# Sheet3.net
KiCad netlist of a schematic drawn in Altium Designer
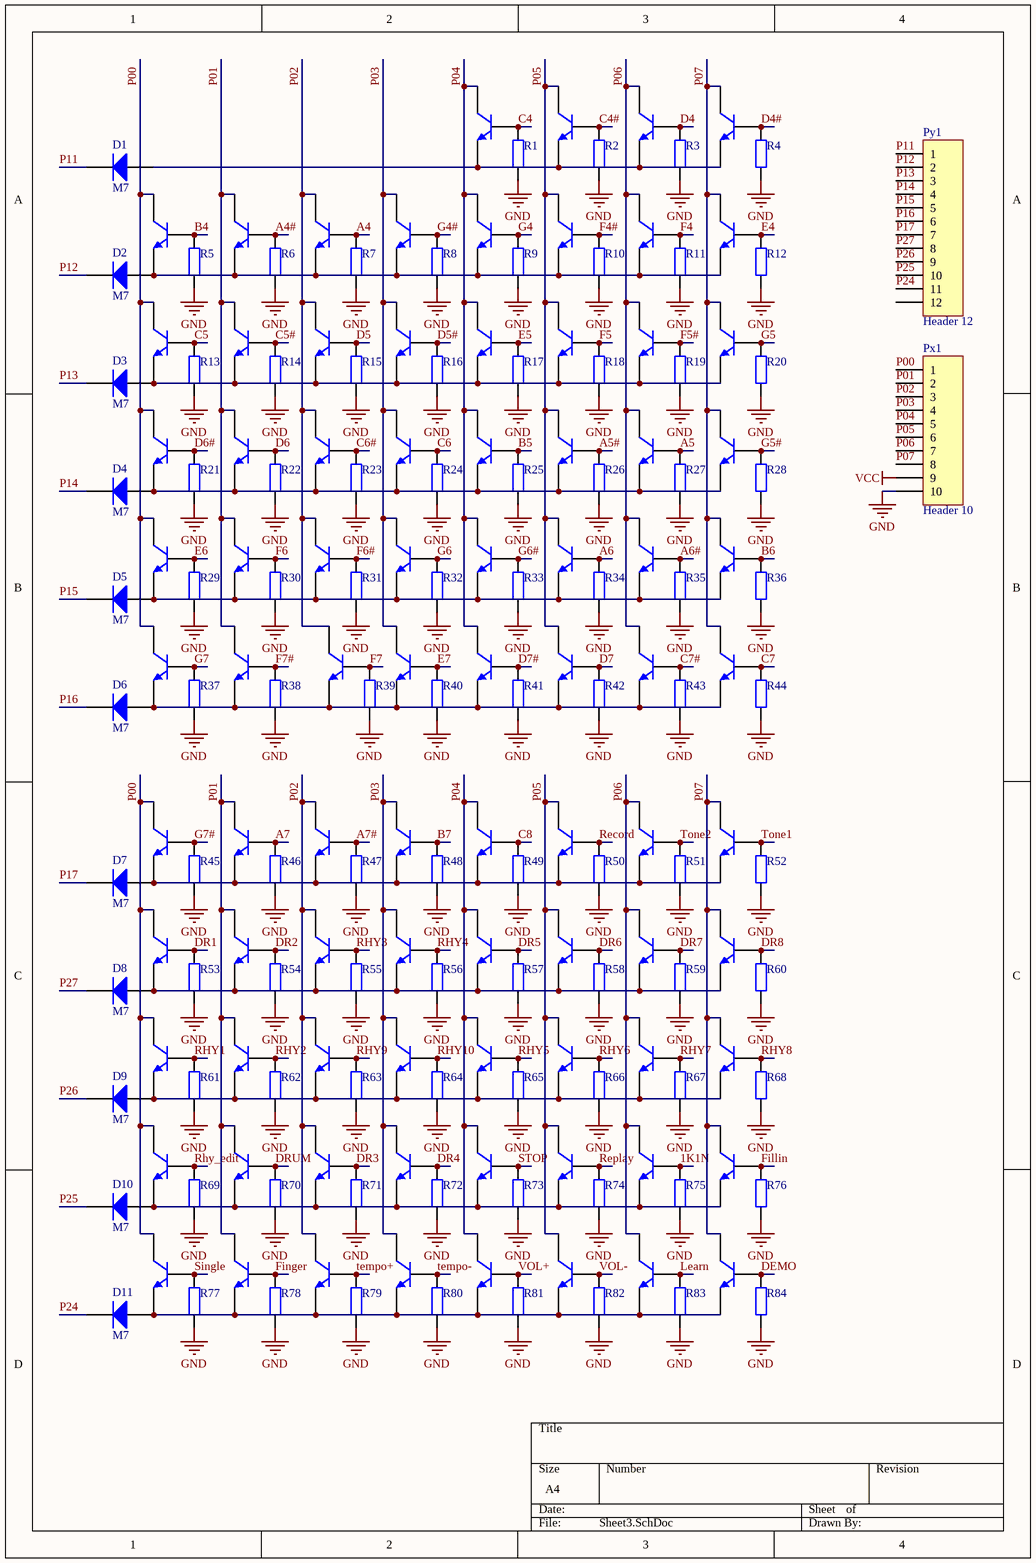
[diagram p0: Sheet3.SchDoc]

(export (version "E")
  (design (tool "Eeschema 10.0.6"))
  (components
    (comp (ref "D1")
      (value "M7")
      (footprint "SMA(DO-214AC)_S1")
      (description "二极管")
      (libsource (lib "Miscellaneous Devices LC") (part "SMA(DO-214AC) M7"))
    )
    (comp (ref "D2")
      (value "M7")
      (footprint "SMA(DO-214AC)_S1")
      (description "二极管")
      (libsource (lib "Miscellaneous Devices LC") (part "SMA(DO-214AC) M7"))
    )
    (comp (ref "D3")
      (value "M7")
      (footprint "SMA(DO-214AC)_S1")
      (description "二极管")
      (libsource (lib "Miscellaneous Devices LC") (part "SMA(DO-214AC) M7"))
    )
    (comp (ref "D4")
      (value "M7")
      (footprint "SMA(DO-214AC)_S1")
      (description "二极管")
      (libsource (lib "Miscellaneous Devices LC") (part "SMA(DO-214AC) M7"))
    )
    (comp (ref "D5")
      (value "M7")
      (footprint "SMA(DO-214AC)_S1")
      (description "二极管")
      (libsource (lib "Miscellaneous Devices LC") (part "SMA(DO-214AC) M7"))
    )
    (comp (ref "D6")
      (value "M7")
      (footprint "SMA(DO-214AC)_S1")
      (description "二极管")
      (libsource (lib "Miscellaneous Devices LC") (part "SMA(DO-214AC) M7"))
    )
    (comp (ref "D7")
      (value "M7")
      (footprint "SMA(DO-214AC)_S1")
      (description "二极管")
      (libsource (lib "Miscellaneous Devices LC") (part "SMA(DO-214AC) M7"))
    )
    (comp (ref "D8")
      (value "M7")
      (footprint "SMA(DO-214AC)_S1")
      (description "二极管")
      (libsource (lib "Miscellaneous Devices LC") (part "SMA(DO-214AC) M7"))
    )
    (comp (ref "D9")
      (value "M7")
      (footprint "SMA(DO-214AC)_S1")
      (description "二极管")
      (libsource (lib "Miscellaneous Devices LC") (part "SMA(DO-214AC) M7"))
    )
    (comp (ref "D10")
      (value "M7")
      (footprint "SMA(DO-214AC)_S1")
      (description "二极管")
      (libsource (lib "Miscellaneous Devices LC") (part "SMA(DO-214AC) M7"))
    )
    (comp (ref "D11")
      (value "M7")
      (footprint "SMA(DO-214AC)_S1")
      (description "二极管")
      (libsource (lib "Miscellaneous Devices LC") (part "SMA(DO-214AC) M7"))
    )
    (comp (ref "Px1")
      (value "Header 10")
      (footprint "FPC1.0-2H-WS-10P")
      (description "Header, 10-Pin")
      (fields (field (name "PUBLISHER") "Altium Limited"))
      (libsource (lib "Miscellaneous Connectors") (part "Header 10"))
    )
    (comp (ref "Py1")
      (value "Header 12")
      (footprint "FPC1.0-2H-WS-12P")
      (description "Header, 12-Pin")
      (fields (field (name "PUBLISHER") "Altium Limited"))
      (libsource (lib "Miscellaneous Connectors") (part "Header 12"))
    )
    (comp (ref "Q1")
      (value "SS8050 Y1")
      (footprint "SOT-23(SOT-23-3)")
      (description "三极管")
      (libsource (lib "Miscellaneous Devices LC") (part "SOT-23 SS8050 Y1"))
    )
    (comp (ref "Q2")
      (value "SS8050 Y1")
      (footprint "SOT-23(SOT-23-3)")
      (description "三极管")
      (libsource (lib "Miscellaneous Devices LC") (part "SOT-23 SS8050 Y1"))
    )
    (comp (ref "Q3")
      (value "SS8050 Y1")
      (footprint "SOT-23(SOT-23-3)")
      (description "三极管")
      (libsource (lib "Miscellaneous Devices LC") (part "SOT-23 SS8050 Y1"))
    )
    (comp (ref "Q4")
      (value "SS8050 Y1")
      (footprint "SOT-23(SOT-23-3)")
      (description "三极管")
      (libsource (lib "Miscellaneous Devices LC") (part "SOT-23 SS8050 Y1"))
    )
    (comp (ref "Q5")
      (value "SS8050 Y1")
      (footprint "SOT-23(SOT-23-3)")
      (description "三极管")
      (libsource (lib "Miscellaneous Devices LC") (part "SOT-23 SS8050 Y1"))
    )
    (comp (ref "Q6")
      (value "SS8050 Y1")
      (footprint "SOT-23(SOT-23-3)")
      (description "三极管")
      (libsource (lib "Miscellaneous Devices LC") (part "SOT-23 SS8050 Y1"))
    )
    (comp (ref "Q7")
      (value "SS8050 Y1")
      (footprint "SOT-23(SOT-23-3)")
      (description "三极管")
      (libsource (lib "Miscellaneous Devices LC") (part "SOT-23 SS8050 Y1"))
    )
    (comp (ref "Q8")
      (value "SS8050 Y1")
      (footprint "SOT-23(SOT-23-3)")
      (description "三极管")
      (libsource (lib "Miscellaneous Devices LC") (part "SOT-23 SS8050 Y1"))
    )
    (comp (ref "Q9")
      (value "SS8050 Y1")
      (footprint "SOT-23(SOT-23-3)")
      (description "三极管")
      (libsource (lib "Miscellaneous Devices LC") (part "SOT-23 SS8050 Y1"))
    )
    (comp (ref "Q10")
      (value "SS8050 Y1")
      (footprint "SOT-23(SOT-23-3)")
      (description "三极管")
      (libsource (lib "Miscellaneous Devices LC") (part "SOT-23 SS8050 Y1"))
    )
    (comp (ref "Q11")
      (value "SS8050 Y1")
      (footprint "SOT-23(SOT-23-3)")
      (description "三极管")
      (libsource (lib "Miscellaneous Devices LC") (part "SOT-23 SS8050 Y1"))
    )
    (comp (ref "Q12")
      (value "SS8050 Y1")
      (footprint "SOT-23(SOT-23-3)")
      (description "三极管")
      (libsource (lib "Miscellaneous Devices LC") (part "SOT-23 SS8050 Y1"))
    )
    (comp (ref "Q13")
      (value "SS8050 Y1")
      (footprint "SOT-23(SOT-23-3)")
      (description "三极管")
      (libsource (lib "Miscellaneous Devices LC") (part "SOT-23 SS8050 Y1"))
    )
    (comp (ref "Q14")
      (value "SS8050 Y1")
      (footprint "SOT-23(SOT-23-3)")
      (description "三极管")
      (libsource (lib "Miscellaneous Devices LC") (part "SOT-23 SS8050 Y1"))
    )
    (comp (ref "Q15")
      (value "SS8050 Y1")
      (footprint "SOT-23(SOT-23-3)")
      (description "三极管")
      (libsource (lib "Miscellaneous Devices LC") (part "SOT-23 SS8050 Y1"))
    )
    (comp (ref "Q16")
      (value "SS8050 Y1")
      (footprint "SOT-23(SOT-23-3)")
      (description "三极管")
      (libsource (lib "Miscellaneous Devices LC") (part "SOT-23 SS8050 Y1"))
    )
    (comp (ref "Q17")
      (value "SS8050 Y1")
      (footprint "SOT-23(SOT-23-3)")
      (description "三极管")
      (libsource (lib "Miscellaneous Devices LC") (part "SOT-23 SS8050 Y1"))
    )
    (comp (ref "Q18")
      (value "SS8050 Y1")
      (footprint "SOT-23(SOT-23-3)")
      (description "三极管")
      (libsource (lib "Miscellaneous Devices LC") (part "SOT-23 SS8050 Y1"))
    )
    (comp (ref "Q19")
      (value "SS8050 Y1")
      (footprint "SOT-23(SOT-23-3)")
      (description "三极管")
      (libsource (lib "Miscellaneous Devices LC") (part "SOT-23 SS8050 Y1"))
    )
    (comp (ref "Q20")
      (value "SS8050 Y1")
      (footprint "SOT-23(SOT-23-3)")
      (description "三极管")
      (libsource (lib "Miscellaneous Devices LC") (part "SOT-23 SS8050 Y1"))
    )
    (comp (ref "Q21")
      (value "SS8050 Y1")
      (footprint "SOT-23(SOT-23-3)")
      (description "三极管")
      (libsource (lib "Miscellaneous Devices LC") (part "SOT-23 SS8050 Y1"))
    )
    (comp (ref "Q22")
      (value "SS8050 Y1")
      (footprint "SOT-23(SOT-23-3)")
      (description "三极管")
      (libsource (lib "Miscellaneous Devices LC") (part "SOT-23 SS8050 Y1"))
    )
    (comp (ref "Q23")
      (value "SS8050 Y1")
      (footprint "SOT-23(SOT-23-3)")
      (description "三极管")
      (libsource (lib "Miscellaneous Devices LC") (part "SOT-23 SS8050 Y1"))
    )
    (comp (ref "Q24")
      (value "SS8050 Y1")
      (footprint "SOT-23(SOT-23-3)")
      (description "三极管")
      (libsource (lib "Miscellaneous Devices LC") (part "SOT-23 SS8050 Y1"))
    )
    (comp (ref "Q25")
      (value "SS8050 Y1")
      (footprint "SOT-23(SOT-23-3)")
      (description "三极管")
      (libsource (lib "Miscellaneous Devices LC") (part "SOT-23 SS8050 Y1"))
    )
    (comp (ref "Q26")
      (value "SS8050 Y1")
      (footprint "SOT-23(SOT-23-3)")
      (description "三极管")
      (libsource (lib "Miscellaneous Devices LC") (part "SOT-23 SS8050 Y1"))
    )
    (comp (ref "Q27")
      (value "SS8050 Y1")
      (footprint "SOT-23(SOT-23-3)")
      (description "三极管")
      (libsource (lib "Miscellaneous Devices LC") (part "SOT-23 SS8050 Y1"))
    )
    (comp (ref "Q28")
      (value "SS8050 Y1")
      (footprint "SOT-23(SOT-23-3)")
      (description "三极管")
      (libsource (lib "Miscellaneous Devices LC") (part "SOT-23 SS8050 Y1"))
    )
    (comp (ref "Q29")
      (value "SS8050 Y1")
      (footprint "SOT-23(SOT-23-3)")
      (description "三极管")
      (libsource (lib "Miscellaneous Devices LC") (part "SOT-23 SS8050 Y1"))
    )
    (comp (ref "Q30")
      (value "SS8050 Y1")
      (footprint "SOT-23(SOT-23-3)")
      (description "三极管")
      (libsource (lib "Miscellaneous Devices LC") (part "SOT-23 SS8050 Y1"))
    )
    (comp (ref "Q31")
      (value "SS8050 Y1")
      (footprint "SOT-23(SOT-23-3)")
      (description "三极管")
      (libsource (lib "Miscellaneous Devices LC") (part "SOT-23 SS8050 Y1"))
    )
    (comp (ref "Q32")
      (value "SS8050 Y1")
      (footprint "SOT-23(SOT-23-3)")
      (description "三极管")
      (libsource (lib "Miscellaneous Devices LC") (part "SOT-23 SS8050 Y1"))
    )
    (comp (ref "Q33")
      (value "SS8050 Y1")
      (footprint "SOT-23(SOT-23-3)")
      (description "三极管")
      (libsource (lib "Miscellaneous Devices LC") (part "SOT-23 SS8050 Y1"))
    )
    (comp (ref "Q34")
      (value "SS8050 Y1")
      (footprint "SOT-23(SOT-23-3)")
      (description "三极管")
      (libsource (lib "Miscellaneous Devices LC") (part "SOT-23 SS8050 Y1"))
    )
    (comp (ref "Q35")
      (value "SS8050 Y1")
      (footprint "SOT-23(SOT-23-3)")
      (description "三极管")
      (libsource (lib "Miscellaneous Devices LC") (part "SOT-23 SS8050 Y1"))
    )
    (comp (ref "Q36")
      (value "SS8050 Y1")
      (footprint "SOT-23(SOT-23-3)")
      (description "三极管")
      (libsource (lib "Miscellaneous Devices LC") (part "SOT-23 SS8050 Y1"))
    )
    (comp (ref "Q37")
      (value "SS8050 Y1")
      (footprint "SOT-23(SOT-23-3)")
      (description "三极管")
      (libsource (lib "Miscellaneous Devices LC") (part "SOT-23 SS8050 Y1"))
    )
    (comp (ref "Q38")
      (value "SS8050 Y1")
      (footprint "SOT-23(SOT-23-3)")
      (description "三极管")
      (libsource (lib "Miscellaneous Devices LC") (part "SOT-23 SS8050 Y1"))
    )
    (comp (ref "Q39")
      (value "SS8050 Y1")
      (footprint "SOT-23(SOT-23-3)")
      (description "三极管")
      (libsource (lib "Miscellaneous Devices LC") (part "SOT-23 SS8050 Y1"))
    )
    (comp (ref "Q40")
      (value "SS8050 Y1")
      (footprint "SOT-23(SOT-23-3)")
      (description "三极管")
      (libsource (lib "Miscellaneous Devices LC") (part "SOT-23 SS8050 Y1"))
    )
    (comp (ref "Q41")
      (value "SS8050 Y1")
      (footprint "SOT-23(SOT-23-3)")
      (description "三极管")
      (libsource (lib "Miscellaneous Devices LC") (part "SOT-23 SS8050 Y1"))
    )
    (comp (ref "Q42")
      (value "SS8050 Y1")
      (footprint "SOT-23(SOT-23-3)")
      (description "三极管")
      (libsource (lib "Miscellaneous Devices LC") (part "SOT-23 SS8050 Y1"))
    )
    (comp (ref "Q43")
      (value "SS8050 Y1")
      (footprint "SOT-23(SOT-23-3)")
      (description "三极管")
      (libsource (lib "Miscellaneous Devices LC") (part "SOT-23 SS8050 Y1"))
    )
    (comp (ref "Q44")
      (value "SS8050 Y1")
      (footprint "SOT-23(SOT-23-3)")
      (description "三极管")
      (libsource (lib "Miscellaneous Devices LC") (part "SOT-23 SS8050 Y1"))
    )
    (comp (ref "Q45")
      (value "SS8050 Y1")
      (footprint "SOT-23(SOT-23-3)")
      (description "三极管")
      (libsource (lib "Miscellaneous Devices LC") (part "SOT-23 SS8050 Y1"))
    )
    (comp (ref "Q46")
      (value "SS8050 Y1")
      (footprint "SOT-23(SOT-23-3)")
      (description "三极管")
      (libsource (lib "Miscellaneous Devices LC") (part "SOT-23 SS8050 Y1"))
    )
    (comp (ref "Q47")
      (value "SS8050 Y1")
      (footprint "SOT-23(SOT-23-3)")
      (description "三极管")
      (libsource (lib "Miscellaneous Devices LC") (part "SOT-23 SS8050 Y1"))
    )
    (comp (ref "Q48")
      (value "SS8050 Y1")
      (footprint "SOT-23(SOT-23-3)")
      (description "三极管")
      (libsource (lib "Miscellaneous Devices LC") (part "SOT-23 SS8050 Y1"))
    )
    (comp (ref "Q49")
      (value "SS8050 Y1")
      (footprint "SOT-23(SOT-23-3)")
      (description "三极管")
      (libsource (lib "Miscellaneous Devices LC") (part "SOT-23 SS8050 Y1"))
    )
    (comp (ref "Q50")
      (value "SS8050 Y1")
      (footprint "SOT-23(SOT-23-3)")
      (description "三极管")
      (libsource (lib "Miscellaneous Devices LC") (part "SOT-23 SS8050 Y1"))
    )
    (comp (ref "Q51")
      (value "SS8050 Y1")
      (footprint "SOT-23(SOT-23-3)")
      (description "三极管")
      (libsource (lib "Miscellaneous Devices LC") (part "SOT-23 SS8050 Y1"))
    )
    (comp (ref "Q52")
      (value "SS8050 Y1")
      (footprint "SOT-23(SOT-23-3)")
      (description "三极管")
      (libsource (lib "Miscellaneous Devices LC") (part "SOT-23 SS8050 Y1"))
    )
    (comp (ref "Q53")
      (value "SS8050 Y1")
      (footprint "SOT-23(SOT-23-3)")
      (description "三极管")
      (libsource (lib "Miscellaneous Devices LC") (part "SOT-23 SS8050 Y1"))
    )
    (comp (ref "Q54")
      (value "SS8050 Y1")
      (footprint "SOT-23(SOT-23-3)")
      (description "三极管")
      (libsource (lib "Miscellaneous Devices LC") (part "SOT-23 SS8050 Y1"))
    )
    (comp (ref "Q55")
      (value "SS8050 Y1")
      (footprint "SOT-23(SOT-23-3)")
      (description "三极管")
      (libsource (lib "Miscellaneous Devices LC") (part "SOT-23 SS8050 Y1"))
    )
    (comp (ref "Q56")
      (value "SS8050 Y1")
      (footprint "SOT-23(SOT-23-3)")
      (description "三极管")
      (libsource (lib "Miscellaneous Devices LC") (part "SOT-23 SS8050 Y1"))
    )
    (comp (ref "Q57")
      (value "SS8050 Y1")
      (footprint "SOT-23(SOT-23-3)")
      (description "三极管")
      (libsource (lib "Miscellaneous Devices LC") (part "SOT-23 SS8050 Y1"))
    )
    (comp (ref "Q58")
      (value "SS8050 Y1")
      (footprint "SOT-23(SOT-23-3)")
      (description "三极管")
      (libsource (lib "Miscellaneous Devices LC") (part "SOT-23 SS8050 Y1"))
    )
    (comp (ref "Q59")
      (value "SS8050 Y1")
      (footprint "SOT-23(SOT-23-3)")
      (description "三极管")
      (libsource (lib "Miscellaneous Devices LC") (part "SOT-23 SS8050 Y1"))
    )
    (comp (ref "Q60")
      (value "SS8050 Y1")
      (footprint "SOT-23(SOT-23-3)")
      (description "三极管")
      (libsource (lib "Miscellaneous Devices LC") (part "SOT-23 SS8050 Y1"))
    )
    (comp (ref "Q61")
      (value "SS8050 Y1")
      (footprint "SOT-23(SOT-23-3)")
      (description "三极管")
      (libsource (lib "Miscellaneous Devices LC") (part "SOT-23 SS8050 Y1"))
    )
    (comp (ref "Q62")
      (value "SS8050 Y1")
      (footprint "SOT-23(SOT-23-3)")
      (description "三极管")
      (libsource (lib "Miscellaneous Devices LC") (part "SOT-23 SS8050 Y1"))
    )
    (comp (ref "Q63")
      (value "SS8050 Y1")
      (footprint "SOT-23(SOT-23-3)")
      (description "三极管")
      (libsource (lib "Miscellaneous Devices LC") (part "SOT-23 SS8050 Y1"))
    )
    (comp (ref "Q64")
      (value "SS8050 Y1")
      (footprint "SOT-23(SOT-23-3)")
      (description "三极管")
      (libsource (lib "Miscellaneous Devices LC") (part "SOT-23 SS8050 Y1"))
    )
    (comp (ref "Q65")
      (value "SS8050 Y1")
      (footprint "SOT-23(SOT-23-3)")
      (description "三极管")
      (libsource (lib "Miscellaneous Devices LC") (part "SOT-23 SS8050 Y1"))
    )
    (comp (ref "Q66")
      (value "SS8050 Y1")
      (footprint "SOT-23(SOT-23-3)")
      (description "三极管")
      (libsource (lib "Miscellaneous Devices LC") (part "SOT-23 SS8050 Y1"))
    )
    (comp (ref "Q67")
      (value "SS8050 Y1")
      (footprint "SOT-23(SOT-23-3)")
      (description "三极管")
      (libsource (lib "Miscellaneous Devices LC") (part "SOT-23 SS8050 Y1"))
    )
    (comp (ref "Q68")
      (value "SS8050 Y1")
      (footprint "SOT-23(SOT-23-3)")
      (description "三极管")
      (libsource (lib "Miscellaneous Devices LC") (part "SOT-23 SS8050 Y1"))
    )
    (comp (ref "Q69")
      (value "SS8050 Y1")
      (footprint "SOT-23(SOT-23-3)")
      (description "三极管")
      (libsource (lib "Miscellaneous Devices LC") (part "SOT-23 SS8050 Y1"))
    )
    (comp (ref "Q70")
      (value "SS8050 Y1")
      (footprint "SOT-23(SOT-23-3)")
      (description "三极管")
      (libsource (lib "Miscellaneous Devices LC") (part "SOT-23 SS8050 Y1"))
    )
    (comp (ref "Q71")
      (value "SS8050 Y1")
      (footprint "SOT-23(SOT-23-3)")
      (description "三极管")
      (libsource (lib "Miscellaneous Devices LC") (part "SOT-23 SS8050 Y1"))
    )
    (comp (ref "Q72")
      (value "SS8050 Y1")
      (footprint "SOT-23(SOT-23-3)")
      (description "三极管")
      (libsource (lib "Miscellaneous Devices LC") (part "SOT-23 SS8050 Y1"))
    )
    (comp (ref "Q73")
      (value "SS8050 Y1")
      (footprint "SOT-23(SOT-23-3)")
      (description "三极管")
      (libsource (lib "Miscellaneous Devices LC") (part "SOT-23 SS8050 Y1"))
    )
    (comp (ref "Q74")
      (value "SS8050 Y1")
      (footprint "SOT-23(SOT-23-3)")
      (description "三极管")
      (libsource (lib "Miscellaneous Devices LC") (part "SOT-23 SS8050 Y1"))
    )
    (comp (ref "Q75")
      (value "SS8050 Y1")
      (footprint "SOT-23(SOT-23-3)")
      (description "三极管")
      (libsource (lib "Miscellaneous Devices LC") (part "SOT-23 SS8050 Y1"))
    )
    (comp (ref "Q76")
      (value "SS8050 Y1")
      (footprint "SOT-23(SOT-23-3)")
      (description "三极管")
      (libsource (lib "Miscellaneous Devices LC") (part "SOT-23 SS8050 Y1"))
    )
    (comp (ref "Q77")
      (value "SS8050 Y1")
      (footprint "SOT-23(SOT-23-3)")
      (description "三极管")
      (libsource (lib "Miscellaneous Devices LC") (part "SOT-23 SS8050 Y1"))
    )
    (comp (ref "Q78")
      (value "SS8050 Y1")
      (footprint "SOT-23(SOT-23-3)")
      (description "三极管")
      (libsource (lib "Miscellaneous Devices LC") (part "SOT-23 SS8050 Y1"))
    )
    (comp (ref "Q79")
      (value "SS8050 Y1")
      (footprint "SOT-23(SOT-23-3)")
      (description "三极管")
      (libsource (lib "Miscellaneous Devices LC") (part "SOT-23 SS8050 Y1"))
    )
    (comp (ref "Q80")
      (value "SS8050 Y1")
      (footprint "SOT-23(SOT-23-3)")
      (description "三极管")
      (libsource (lib "Miscellaneous Devices LC") (part "SOT-23 SS8050 Y1"))
    )
    (comp (ref "Q81")
      (value "SS8050 Y1")
      (footprint "SOT-23(SOT-23-3)")
      (description "三极管")
      (libsource (lib "Miscellaneous Devices LC") (part "SOT-23 SS8050 Y1"))
    )
    (comp (ref "Q82")
      (value "SS8050 Y1")
      (footprint "SOT-23(SOT-23-3)")
      (description "三极管")
      (libsource (lib "Miscellaneous Devices LC") (part "SOT-23 SS8050 Y1"))
    )
    (comp (ref "Q83")
      (value "SS8050 Y1")
      (footprint "SOT-23(SOT-23-3)")
      (description "三极管")
      (libsource (lib "Miscellaneous Devices LC") (part "SOT-23 SS8050 Y1"))
    )
    (comp (ref "Q84")
      (value "SS8050 Y1")
      (footprint "SOT-23(SOT-23-3)")
      (description "三极管")
      (libsource (lib "Miscellaneous Devices LC") (part "SOT-23 SS8050 Y1"))
    )
    (comp (ref "R1")
      (value "10KΩ (1002) ±1%")
      (footprint "0603_R")
      (description "贴片电阻")
      (libsource (lib "Miscellaneous Devices LC") (part "0603 10KΩ (1002) 1%"))
    )
    (comp (ref "R2")
      (value "10KΩ (1002) ±1%")
      (footprint "0603_R")
      (description "贴片电阻")
      (libsource (lib "Miscellaneous Devices LC") (part "0603 10KΩ (1002) 1%"))
    )
    (comp (ref "R3")
      (value "10KΩ (1002) ±1%")
      (footprint "0603_R")
      (description "贴片电阻")
      (libsource (lib "Miscellaneous Devices LC") (part "0603 10KΩ (1002) 1%"))
    )
    (comp (ref "R4")
      (value "10KΩ (1002) ±1%")
      (footprint "0603_R")
      (description "贴片电阻")
      (libsource (lib "Miscellaneous Devices LC") (part "0603 10KΩ (1002) 1%"))
    )
    (comp (ref "R5")
      (value "10KΩ (1002) ±1%")
      (footprint "0603_R")
      (description "贴片电阻")
      (libsource (lib "Miscellaneous Devices LC") (part "0603 10KΩ (1002) 1%"))
    )
    (comp (ref "R6")
      (value "10KΩ (1002) ±1%")
      (footprint "0603_R")
      (description "贴片电阻")
      (libsource (lib "Miscellaneous Devices LC") (part "0603 10KΩ (1002) 1%"))
    )
    (comp (ref "R7")
      (value "10KΩ (1002) ±1%")
      (footprint "0603_R")
      (description "贴片电阻")
      (libsource (lib "Miscellaneous Devices LC") (part "0603 10KΩ (1002) 1%"))
    )
    (comp (ref "R8")
      (value "10KΩ (1002) ±1%")
      (footprint "0603_R")
      (description "贴片电阻")
      (libsource (lib "Miscellaneous Devices LC") (part "0603 10KΩ (1002) 1%"))
    )
    (comp (ref "R9")
      (value "10KΩ (1002) ±1%")
      (footprint "0603_R")
      (description "贴片电阻")
      (libsource (lib "Miscellaneous Devices LC") (part "0603 10KΩ (1002) 1%"))
    )
    (comp (ref "R10")
      (value "10KΩ (1002) ±1%")
      (footprint "0603_R")
      (description "贴片电阻")
      (libsource (lib "Miscellaneous Devices LC") (part "0603 10KΩ (1002) 1%"))
    )
    (comp (ref "R11")
      (value "10KΩ (1002) ±1%")
      (footprint "0603_R")
      (description "贴片电阻")
      (libsource (lib "Miscellaneous Devices LC") (part "0603 10KΩ (1002) 1%"))
    )
    (comp (ref "R12")
      (value "10KΩ (1002) ±1%")
      (footprint "0603_R")
      (description "贴片电阻")
      (libsource (lib "Miscellaneous Devices LC") (part "0603 10KΩ (1002) 1%"))
    )
    (comp (ref "R13")
      (value "10KΩ (1002) ±1%")
      (footprint "0603_R")
      (description "贴片电阻")
      (libsource (lib "Miscellaneous Devices LC") (part "0603 10KΩ (1002) 1%"))
    )
    (comp (ref "R14")
      (value "10KΩ (1002) ±1%")
      (footprint "0603_R")
      (description "贴片电阻")
      (libsource (lib "Miscellaneous Devices LC") (part "0603 10KΩ (1002) 1%"))
    )
    (comp (ref "R15")
      (value "10KΩ (1002) ±1%")
      (footprint "0603_R")
      (description "贴片电阻")
      (libsource (lib "Miscellaneous Devices LC") (part "0603 10KΩ (1002) 1%"))
    )
    (comp (ref "R16")
      (value "10KΩ (1002) ±1%")
      (footprint "0603_R")
      (description "贴片电阻")
      (libsource (lib "Miscellaneous Devices LC") (part "0603 10KΩ (1002) 1%"))
    )
    (comp (ref "R17")
      (value "10KΩ (1002) ±1%")
      (footprint "0603_R")
      (description "贴片电阻")
      (libsource (lib "Miscellaneous Devices LC") (part "0603 10KΩ (1002) 1%"))
    )
    (comp (ref "R18")
      (value "10KΩ (1002) ±1%")
      (footprint "0603_R")
      (description "贴片电阻")
      (libsource (lib "Miscellaneous Devices LC") (part "0603 10KΩ (1002) 1%"))
    )
    (comp (ref "R19")
      (value "10KΩ (1002) ±1%")
      (footprint "0603_R")
      (description "贴片电阻")
      (libsource (lib "Miscellaneous Devices LC") (part "0603 10KΩ (1002) 1%"))
    )
    (comp (ref "R20")
      (value "10KΩ (1002) ±1%")
      (footprint "0603_R")
      (description "贴片电阻")
      (libsource (lib "Miscellaneous Devices LC") (part "0603 10KΩ (1002) 1%"))
    )
    (comp (ref "R21")
      (value "10KΩ (1002) ±1%")
      (footprint "0603_R")
      (description "贴片电阻")
      (libsource (lib "Miscellaneous Devices LC") (part "0603 10KΩ (1002) 1%"))
    )
    (comp (ref "R22")
      (value "10KΩ (1002) ±1%")
      (footprint "0603_R")
      (description "贴片电阻")
      (libsource (lib "Miscellaneous Devices LC") (part "0603 10KΩ (1002) 1%"))
    )
    (comp (ref "R23")
      (value "10KΩ (1002) ±1%")
      (footprint "0603_R")
      (description "贴片电阻")
      (libsource (lib "Miscellaneous Devices LC") (part "0603 10KΩ (1002) 1%"))
    )
    (comp (ref "R24")
      (value "10KΩ (1002) ±1%")
      (footprint "0603_R")
      (description "贴片电阻")
      (libsource (lib "Miscellaneous Devices LC") (part "0603 10KΩ (1002) 1%"))
    )
    (comp (ref "R25")
      (value "10KΩ (1002) ±1%")
      (footprint "0603_R")
      (description "贴片电阻")
      (libsource (lib "Miscellaneous Devices LC") (part "0603 10KΩ (1002) 1%"))
    )
    (comp (ref "R26")
      (value "10KΩ (1002) ±1%")
      (footprint "0603_R")
      (description "贴片电阻")
      (libsource (lib "Miscellaneous Devices LC") (part "0603 10KΩ (1002) 1%"))
    )
    (comp (ref "R27")
      (value "10KΩ (1002) ±1%")
      (footprint "0603_R")
      (description "贴片电阻")
      (libsource (lib "Miscellaneous Devices LC") (part "0603 10KΩ (1002) 1%"))
    )
    (comp (ref "R28")
      (value "10KΩ (1002) ±1%")
      (footprint "0603_R")
      (description "贴片电阻")
      (libsource (lib "Miscellaneous Devices LC") (part "0603 10KΩ (1002) 1%"))
    )
    (comp (ref "R29")
      (value "10KΩ (1002) ±1%")
      (footprint "0603_R")
      (description "贴片电阻")
      (libsource (lib "Miscellaneous Devices LC") (part "0603 10KΩ (1002) 1%"))
    )
    (comp (ref "R30")
      (value "10KΩ (1002) ±1%")
      (footprint "0603_R")
      (description "贴片电阻")
      (libsource (lib "Miscellaneous Devices LC") (part "0603 10KΩ (1002) 1%"))
    )
    (comp (ref "R31")
      (value "10KΩ (1002) ±1%")
      (footprint "0603_R")
      (description "贴片电阻")
      (libsource (lib "Miscellaneous Devices LC") (part "0603 10KΩ (1002) 1%"))
    )
    (comp (ref "R32")
      (value "10KΩ (1002) ±1%")
      (footprint "0603_R")
      (description "贴片电阻")
      (libsource (lib "Miscellaneous Devices LC") (part "0603 10KΩ (1002) 1%"))
    )
    (comp (ref "R33")
      (value "10KΩ (1002) ±1%")
      (footprint "0603_R")
      (description "贴片电阻")
      (libsource (lib "Miscellaneous Devices LC") (part "0603 10KΩ (1002) 1%"))
    )
    (comp (ref "R34")
      (value "10KΩ (1002) ±1%")
      (footprint "0603_R")
      (description "贴片电阻")
      (libsource (lib "Miscellaneous Devices LC") (part "0603 10KΩ (1002) 1%"))
    )
    (comp (ref "R35")
      (value "10KΩ (1002) ±1%")
      (footprint "0603_R")
      (description "贴片电阻")
      (libsource (lib "Miscellaneous Devices LC") (part "0603 10KΩ (1002) 1%"))
    )
    (comp (ref "R36")
      (value "10KΩ (1002) ±1%")
      (footprint "0603_R")
      (description "贴片电阻")
      (libsource (lib "Miscellaneous Devices LC") (part "0603 10KΩ (1002) 1%"))
    )
    (comp (ref "R37")
      (value "10KΩ (1002) ±1%")
      (footprint "0603_R")
      (description "贴片电阻")
      (libsource (lib "Miscellaneous Devices LC") (part "0603 10KΩ (1002) 1%"))
    )
    (comp (ref "R38")
      (value "10KΩ (1002) ±1%")
      (footprint "0603_R")
      (description "贴片电阻")
      (libsource (lib "Miscellaneous Devices LC") (part "0603 10KΩ (1002) 1%"))
    )
    (comp (ref "R39")
      (value "10KΩ (1002) ±1%")
      (footprint "0603_R")
      (description "贴片电阻")
      (libsource (lib "Miscellaneous Devices LC") (part "0603 10KΩ (1002) 1%"))
    )
    (comp (ref "R40")
      (value "10KΩ (1002) ±1%")
      (footprint "0603_R")
      (description "贴片电阻")
      (libsource (lib "Miscellaneous Devices LC") (part "0603 10KΩ (1002) 1%"))
    )
    (comp (ref "R41")
      (value "10KΩ (1002) ±1%")
      (footprint "0603_R")
      (description "贴片电阻")
      (libsource (lib "Miscellaneous Devices LC") (part "0603 10KΩ (1002) 1%"))
    )
    (comp (ref "R42")
      (value "10KΩ (1002) ±1%")
      (footprint "0603_R")
      (description "贴片电阻")
      (libsource (lib "Miscellaneous Devices LC") (part "0603 10KΩ (1002) 1%"))
    )
    (comp (ref "R43")
      (value "10KΩ (1002) ±1%")
      (footprint "0603_R")
      (description "贴片电阻")
      (libsource (lib "Miscellaneous Devices LC") (part "0603 10KΩ (1002) 1%"))
    )
    (comp (ref "R44")
      (value "10KΩ (1002) ±1%")
      (footprint "0603_R")
      (description "贴片电阻")
      (libsource (lib "Miscellaneous Devices LC") (part "0603 10KΩ (1002) 1%"))
    )
    (comp (ref "R45")
      (value "10KΩ (1002) ±1%")
      (footprint "0603_R")
      (description "贴片电阻")
      (libsource (lib "Miscellaneous Devices LC") (part "0603 10KΩ (1002) 1%"))
    )
    (comp (ref "R46")
      (value "10KΩ (1002) ±1%")
      (footprint "0603_R")
      (description "贴片电阻")
      (libsource (lib "Miscellaneous Devices LC") (part "0603 10KΩ (1002) 1%"))
    )
    (comp (ref "R47")
      (value "10KΩ (1002) ±1%")
      (footprint "0603_R")
      (description "贴片电阻")
      (libsource (lib "Miscellaneous Devices LC") (part "0603 10KΩ (1002) 1%"))
    )
    (comp (ref "R48")
      (value "10KΩ (1002) ±1%")
      (footprint "0603_R")
      (description "贴片电阻")
      (libsource (lib "Miscellaneous Devices LC") (part "0603 10KΩ (1002) 1%"))
    )
    (comp (ref "R49")
      (value "10KΩ (1002) ±1%")
      (footprint "0603_R")
      (description "贴片电阻")
      (libsource (lib "Miscellaneous Devices LC") (part "0603 10KΩ (1002) 1%"))
    )
    (comp (ref "R50")
      (value "10KΩ (1002) ±1%")
      (footprint "0603_R")
      (description "贴片电阻")
      (libsource (lib "Miscellaneous Devices LC") (part "0603 10KΩ (1002) 1%"))
    )
    (comp (ref "R51")
      (value "10KΩ (1002) ±1%")
      (footprint "0603_R")
      (description "贴片电阻")
      (libsource (lib "Miscellaneous Devices LC") (part "0603 10KΩ (1002) 1%"))
    )
    (comp (ref "R52")
      (value "10KΩ (1002) ±1%")
      (footprint "0603_R")
      (description "贴片电阻")
      (libsource (lib "Miscellaneous Devices LC") (part "0603 10KΩ (1002) 1%"))
    )
    (comp (ref "R53")
      (value "10KΩ (1002) ±1%")
      (footprint "0603_R")
      (description "贴片电阻")
      (libsource (lib "Miscellaneous Devices LC") (part "0603 10KΩ (1002) 1%"))
    )
    (comp (ref "R54")
      (value "10KΩ (1002) ±1%")
      (footprint "0603_R")
      (description "贴片电阻")
      (libsource (lib "Miscellaneous Devices LC") (part "0603 10KΩ (1002) 1%"))
    )
    (comp (ref "R55")
      (value "10KΩ (1002) ±1%")
      (footprint "0603_R")
      (description "贴片电阻")
      (libsource (lib "Miscellaneous Devices LC") (part "0603 10KΩ (1002) 1%"))
    )
    (comp (ref "R56")
      (value "10KΩ (1002) ±1%")
      (footprint "0603_R")
      (description "贴片电阻")
      (libsource (lib "Miscellaneous Devices LC") (part "0603 10KΩ (1002) 1%"))
    )
    (comp (ref "R57")
      (value "10KΩ (1002) ±1%")
      (footprint "0603_R")
      (description "贴片电阻")
      (libsource (lib "Miscellaneous Devices LC") (part "0603 10KΩ (1002) 1%"))
    )
    (comp (ref "R58")
      (value "10KΩ (1002) ±1%")
      (footprint "0603_R")
      (description "贴片电阻")
      (libsource (lib "Miscellaneous Devices LC") (part "0603 10KΩ (1002) 1%"))
    )
    (comp (ref "R59")
      (value "10KΩ (1002) ±1%")
      (footprint "0603_R")
      (description "贴片电阻")
      (libsource (lib "Miscellaneous Devices LC") (part "0603 10KΩ (1002) 1%"))
    )
    (comp (ref "R60")
      (value "10KΩ (1002) ±1%")
      (footprint "0603_R")
      (description "贴片电阻")
      (libsource (lib "Miscellaneous Devices LC") (part "0603 10KΩ (1002) 1%"))
    )
    (comp (ref "R61")
      (value "10KΩ (1002) ±1%")
      (footprint "0603_R")
      (description "贴片电阻")
      (libsource (lib "Miscellaneous Devices LC") (part "0603 10KΩ (1002) 1%"))
    )
    (comp (ref "R62")
      (value "10KΩ (1002) ±1%")
      (footprint "0603_R")
      (description "贴片电阻")
      (libsource (lib "Miscellaneous Devices LC") (part "0603 10KΩ (1002) 1%"))
    )
    (comp (ref "R63")
      (value "10KΩ (1002) ±1%")
      (footprint "0603_R")
      (description "贴片电阻")
      (libsource (lib "Miscellaneous Devices LC") (part "0603 10KΩ (1002) 1%"))
    )
    (comp (ref "R64")
      (value "10KΩ (1002) ±1%")
      (footprint "0603_R")
      (description "贴片电阻")
      (libsource (lib "Miscellaneous Devices LC") (part "0603 10KΩ (1002) 1%"))
    )
    (comp (ref "R65")
      (value "10KΩ (1002) ±1%")
      (footprint "0603_R")
      (description "贴片电阻")
      (libsource (lib "Miscellaneous Devices LC") (part "0603 10KΩ (1002) 1%"))
    )
    (comp (ref "R66")
      (value "10KΩ (1002) ±1%")
      (footprint "0603_R")
      (description "贴片电阻")
      (libsource (lib "Miscellaneous Devices LC") (part "0603 10KΩ (1002) 1%"))
    )
    (comp (ref "R67")
      (value "10KΩ (1002) ±1%")
      (footprint "0603_R")
      (description "贴片电阻")
      (libsource (lib "Miscellaneous Devices LC") (part "0603 10KΩ (1002) 1%"))
    )
    (comp (ref "R68")
      (value "10KΩ (1002) ±1%")
      (footprint "0603_R")
      (description "贴片电阻")
      (libsource (lib "Miscellaneous Devices LC") (part "0603 10KΩ (1002) 1%"))
    )
    (comp (ref "R69")
      (value "10KΩ (1002) ±1%")
      (footprint "0603_R")
      (description "贴片电阻")
      (libsource (lib "Miscellaneous Devices LC") (part "0603 10KΩ (1002) 1%"))
    )
    (comp (ref "R70")
      (value "10KΩ (1002) ±1%")
      (footprint "0603_R")
      (description "贴片电阻")
      (libsource (lib "Miscellaneous Devices LC") (part "0603 10KΩ (1002) 1%"))
    )
    (comp (ref "R71")
      (value "10KΩ (1002) ±1%")
      (footprint "0603_R")
      (description "贴片电阻")
      (libsource (lib "Miscellaneous Devices LC") (part "0603 10KΩ (1002) 1%"))
    )
    (comp (ref "R72")
      (value "10KΩ (1002) ±1%")
      (footprint "0603_R")
      (description "贴片电阻")
      (libsource (lib "Miscellaneous Devices LC") (part "0603 10KΩ (1002) 1%"))
    )
    (comp (ref "R73")
      (value "10KΩ (1002) ±1%")
      (footprint "0603_R")
      (description "贴片电阻")
      (libsource (lib "Miscellaneous Devices LC") (part "0603 10KΩ (1002) 1%"))
    )
    (comp (ref "R74")
      (value "10KΩ (1002) ±1%")
      (footprint "0603_R")
      (description "贴片电阻")
      (libsource (lib "Miscellaneous Devices LC") (part "0603 10KΩ (1002) 1%"))
    )
    (comp (ref "R75")
      (value "10KΩ (1002) ±1%")
      (footprint "0603_R")
      (description "贴片电阻")
      (libsource (lib "Miscellaneous Devices LC") (part "0603 10KΩ (1002) 1%"))
    )
    (comp (ref "R76")
      (value "10KΩ (1002) ±1%")
      (footprint "0603_R")
      (description "贴片电阻")
      (libsource (lib "Miscellaneous Devices LC") (part "0603 10KΩ (1002) 1%"))
    )
    (comp (ref "R77")
      (value "10KΩ (1002) ±1%")
      (footprint "0603_R")
      (description "贴片电阻")
      (libsource (lib "Miscellaneous Devices LC") (part "0603 10KΩ (1002) 1%"))
    )
    (comp (ref "R78")
      (value "10KΩ (1002) ±1%")
      (footprint "0603_R")
      (description "贴片电阻")
      (libsource (lib "Miscellaneous Devices LC") (part "0603 10KΩ (1002) 1%"))
    )
    (comp (ref "R79")
      (value "10KΩ (1002) ±1%")
      (footprint "0603_R")
      (description "贴片电阻")
      (libsource (lib "Miscellaneous Devices LC") (part "0603 10KΩ (1002) 1%"))
    )
    (comp (ref "R80")
      (value "10KΩ (1002) ±1%")
      (footprint "0603_R")
      (description "贴片电阻")
      (libsource (lib "Miscellaneous Devices LC") (part "0603 10KΩ (1002) 1%"))
    )
    (comp (ref "R81")
      (value "10KΩ (1002) ±1%")
      (footprint "0603_R")
      (description "贴片电阻")
      (libsource (lib "Miscellaneous Devices LC") (part "0603 10KΩ (1002) 1%"))
    )
    (comp (ref "R82")
      (value "10KΩ (1002) ±1%")
      (footprint "0603_R")
      (description "贴片电阻")
      (libsource (lib "Miscellaneous Devices LC") (part "0603 10KΩ (1002) 1%"))
    )
    (comp (ref "R83")
      (value "10KΩ (1002) ±1%")
      (footprint "0603_R")
      (description "贴片电阻")
      (libsource (lib "Miscellaneous Devices LC") (part "0603 10KΩ (1002) 1%"))
    )
    (comp (ref "R84")
      (value "10KΩ (1002) ±1%")
      (footprint "0603_R")
      (description "贴片电阻")
      (libsource (lib "Miscellaneous Devices LC") (part "0603 10KΩ (1002) 1%"))
    )
  )
  (nets
    (net (code "1") (name "/1K1N") (class "Default")
      (node (ref "Q75") (pin "1") (pinfunction "B_1") (pintype "passive"))
      (node (ref "R75") (pin "2") (pinfunction "2_2") (pintype "passive"))
    )
    (net (code "2") (name "/A4") (class "Default")
      (node (ref "Q7") (pin "1") (pinfunction "B_1") (pintype "passive"))
      (node (ref "R7") (pin "2") (pinfunction "2_2") (pintype "passive"))
    )
    (net (code "3") (name "/A4#") (class "Default")
      (node (ref "Q6") (pin "1") (pinfunction "B_1") (pintype "passive"))
      (node (ref "R6") (pin "2") (pinfunction "2_2") (pintype "passive"))
    )
    (net (code "4") (name "/A5") (class "Default")
      (node (ref "Q27") (pin "1") (pinfunction "B_1") (pintype "passive"))
      (node (ref "R27") (pin "2") (pinfunction "2_2") (pintype "passive"))
    )
    (net (code "5") (name "/A5#") (class "Default")
      (node (ref "Q26") (pin "1") (pinfunction "B_1") (pintype "passive"))
      (node (ref "R26") (pin "2") (pinfunction "2_2") (pintype "passive"))
    )
    (net (code "6") (name "/A6") (class "Default")
      (node (ref "Q34") (pin "1") (pinfunction "B_1") (pintype "passive"))
      (node (ref "R34") (pin "2") (pinfunction "2_2") (pintype "passive"))
    )
    (net (code "7") (name "/A6#") (class "Default")
      (node (ref "Q35") (pin "1") (pinfunction "B_1") (pintype "passive"))
      (node (ref "R35") (pin "2") (pinfunction "2_2") (pintype "passive"))
    )
    (net (code "8") (name "/A7") (class "Default")
      (node (ref "Q46") (pin "1") (pinfunction "B_1") (pintype "passive"))
      (node (ref "R46") (pin "2") (pinfunction "2_2") (pintype "passive"))
    )
    (net (code "9") (name "/A7#") (class "Default")
      (node (ref "Q47") (pin "1") (pinfunction "B_1") (pintype "passive"))
      (node (ref "R47") (pin "2") (pinfunction "2_2") (pintype "passive"))
    )
    (net (code "10") (name "/B4") (class "Default")
      (node (ref "Q5") (pin "1") (pinfunction "B_1") (pintype "passive"))
      (node (ref "R5") (pin "2") (pinfunction "2_2") (pintype "passive"))
    )
    (net (code "11") (name "/B5") (class "Default")
      (node (ref "Q25") (pin "1") (pinfunction "B_1") (pintype "passive"))
      (node (ref "R25") (pin "2") (pinfunction "2_2") (pintype "passive"))
    )
    (net (code "12") (name "/B6") (class "Default")
      (node (ref "Q36") (pin "1") (pinfunction "B_1") (pintype "passive"))
      (node (ref "R36") (pin "2") (pinfunction "2_2") (pintype "passive"))
    )
    (net (code "13") (name "/B7") (class "Default")
      (node (ref "Q48") (pin "1") (pinfunction "B_1") (pintype "passive"))
      (node (ref "R48") (pin "2") (pinfunction "2_2") (pintype "passive"))
    )
    (net (code "14") (name "/C4") (class "Default")
      (node (ref "Q1") (pin "1") (pinfunction "B_1") (pintype "passive"))
      (node (ref "R1") (pin "2") (pinfunction "2_2") (pintype "passive"))
    )
    (net (code "15") (name "/C4#") (class "Default")
      (node (ref "Q2") (pin "1") (pinfunction "B_1") (pintype "passive"))
      (node (ref "R2") (pin "2") (pinfunction "2_2") (pintype "passive"))
    )
    (net (code "16") (name "/C5") (class "Default")
      (node (ref "Q13") (pin "1") (pinfunction "B_1") (pintype "passive"))
      (node (ref "R13") (pin "2") (pinfunction "2_2") (pintype "passive"))
    )
    (net (code "17") (name "/C5#") (class "Default")
      (node (ref "Q14") (pin "1") (pinfunction "B_1") (pintype "passive"))
      (node (ref "R14") (pin "2") (pinfunction "2_2") (pintype "passive"))
    )
    (net (code "18") (name "/C6") (class "Default")
      (node (ref "Q24") (pin "1") (pinfunction "B_1") (pintype "passive"))
      (node (ref "R24") (pin "2") (pinfunction "2_2") (pintype "passive"))
    )
    (net (code "19") (name "/C6#") (class "Default")
      (node (ref "Q23") (pin "1") (pinfunction "B_1") (pintype "passive"))
      (node (ref "R23") (pin "2") (pinfunction "2_2") (pintype "passive"))
    )
    (net (code "20") (name "/C7") (class "Default")
      (node (ref "Q44") (pin "1") (pinfunction "B_1") (pintype "passive"))
      (node (ref "R44") (pin "2") (pinfunction "2_2") (pintype "passive"))
    )
    (net (code "21") (name "/C7#") (class "Default")
      (node (ref "Q43") (pin "1") (pinfunction "B_1") (pintype "passive"))
      (node (ref "R43") (pin "2") (pinfunction "2_2") (pintype "passive"))
    )
    (net (code "22") (name "/C8") (class "Default")
      (node (ref "Q49") (pin "1") (pinfunction "B_1") (pintype "passive"))
      (node (ref "R49") (pin "2") (pinfunction "2_2") (pintype "passive"))
    )
    (net (code "23") (name "/D4") (class "Default")
      (node (ref "Q3") (pin "1") (pinfunction "B_1") (pintype "passive"))
      (node (ref "R3") (pin "2") (pinfunction "2_2") (pintype "passive"))
    )
    (net (code "24") (name "/D4#") (class "Default")
      (node (ref "Q4") (pin "1") (pinfunction "B_1") (pintype "passive"))
      (node (ref "R4") (pin "2") (pinfunction "2_2") (pintype "passive"))
    )
    (net (code "25") (name "/D5") (class "Default")
      (node (ref "Q15") (pin "1") (pinfunction "B_1") (pintype "passive"))
      (node (ref "R15") (pin "2") (pinfunction "2_2") (pintype "passive"))
    )
    (net (code "26") (name "/D5#") (class "Default")
      (node (ref "Q16") (pin "1") (pinfunction "B_1") (pintype "passive"))
      (node (ref "R16") (pin "2") (pinfunction "2_2") (pintype "passive"))
    )
    (net (code "27") (name "/D6") (class "Default")
      (node (ref "Q22") (pin "1") (pinfunction "B_1") (pintype "passive"))
      (node (ref "R22") (pin "2") (pinfunction "2_2") (pintype "passive"))
    )
    (net (code "28") (name "/D6#") (class "Default")
      (node (ref "Q21") (pin "1") (pinfunction "B_1") (pintype "passive"))
      (node (ref "R21") (pin "2") (pinfunction "2_2") (pintype "passive"))
    )
    (net (code "29") (name "/D7") (class "Default")
      (node (ref "Q42") (pin "1") (pinfunction "B_1") (pintype "passive"))
      (node (ref "R42") (pin "2") (pinfunction "2_2") (pintype "passive"))
    )
    (net (code "30") (name "/D7#") (class "Default")
      (node (ref "Q41") (pin "1") (pinfunction "B_1") (pintype "passive"))
      (node (ref "R41") (pin "2") (pinfunction "2_2") (pintype "passive"))
    )
    (net (code "31") (name "/DEMO") (class "Default")
      (node (ref "Q84") (pin "1") (pinfunction "B_1") (pintype "passive"))
      (node (ref "R84") (pin "2") (pinfunction "2_2") (pintype "passive"))
    )
    (net (code "32") (name "/DR1") (class "Default")
      (node (ref "Q53") (pin "1") (pinfunction "B_1") (pintype "passive"))
      (node (ref "R53") (pin "2") (pinfunction "2_2") (pintype "passive"))
    )
    (net (code "33") (name "/DR2") (class "Default")
      (node (ref "Q54") (pin "1") (pinfunction "B_1") (pintype "passive"))
      (node (ref "R54") (pin "2") (pinfunction "2_2") (pintype "passive"))
    )
    (net (code "34") (name "/DR3") (class "Default")
      (node (ref "Q71") (pin "1") (pinfunction "B_1") (pintype "passive"))
      (node (ref "R71") (pin "2") (pinfunction "2_2") (pintype "passive"))
    )
    (net (code "35") (name "/DR4") (class "Default")
      (node (ref "Q72") (pin "1") (pinfunction "B_1") (pintype "passive"))
      (node (ref "R72") (pin "2") (pinfunction "2_2") (pintype "passive"))
    )
    (net (code "36") (name "/DR5") (class "Default")
      (node (ref "Q57") (pin "1") (pinfunction "B_1") (pintype "passive"))
      (node (ref "R57") (pin "2") (pinfunction "2_2") (pintype "passive"))
    )
    (net (code "37") (name "/DR6") (class "Default")
      (node (ref "Q58") (pin "1") (pinfunction "B_1") (pintype "passive"))
      (node (ref "R58") (pin "2") (pinfunction "2_2") (pintype "passive"))
    )
    (net (code "38") (name "/DR7") (class "Default")
      (node (ref "Q59") (pin "1") (pinfunction "B_1") (pintype "passive"))
      (node (ref "R59") (pin "2") (pinfunction "2_2") (pintype "passive"))
    )
    (net (code "39") (name "/DR8") (class "Default")
      (node (ref "Q60") (pin "1") (pinfunction "B_1") (pintype "passive"))
      (node (ref "R60") (pin "2") (pinfunction "2_2") (pintype "passive"))
    )
    (net (code "40") (name "/DRUM") (class "Default")
      (node (ref "Q70") (pin "1") (pinfunction "B_1") (pintype "passive"))
      (node (ref "R70") (pin "2") (pinfunction "2_2") (pintype "passive"))
    )
    (net (code "41") (name "/E4") (class "Default")
      (node (ref "Q12") (pin "1") (pinfunction "B_1") (pintype "passive"))
      (node (ref "R12") (pin "2") (pinfunction "2_2") (pintype "passive"))
    )
    (net (code "42") (name "/E5") (class "Default")
      (node (ref "Q17") (pin "1") (pinfunction "B_1") (pintype "passive"))
      (node (ref "R17") (pin "2") (pinfunction "2_2") (pintype "passive"))
    )
    (net (code "43") (name "/E6") (class "Default")
      (node (ref "Q29") (pin "1") (pinfunction "B_1") (pintype "passive"))
      (node (ref "R29") (pin "2") (pinfunction "2_2") (pintype "passive"))
    )
    (net (code "44") (name "/E7") (class "Default")
      (node (ref "Q40") (pin "1") (pinfunction "B_1") (pintype "passive"))
      (node (ref "R40") (pin "2") (pinfunction "2_2") (pintype "passive"))
    )
    (net (code "45") (name "/F4") (class "Default")
      (node (ref "Q11") (pin "1") (pinfunction "B_1") (pintype "passive"))
      (node (ref "R11") (pin "2") (pinfunction "2_2") (pintype "passive"))
    )
    (net (code "46") (name "/F4#") (class "Default")
      (node (ref "Q10") (pin "1") (pinfunction "B_1") (pintype "passive"))
      (node (ref "R10") (pin "2") (pinfunction "2_2") (pintype "passive"))
    )
    (net (code "47") (name "/F5") (class "Default")
      (node (ref "Q18") (pin "1") (pinfunction "B_1") (pintype "passive"))
      (node (ref "R18") (pin "2") (pinfunction "2_2") (pintype "passive"))
    )
    (net (code "48") (name "/F5#") (class "Default")
      (node (ref "Q19") (pin "1") (pinfunction "B_1") (pintype "passive"))
      (node (ref "R19") (pin "2") (pinfunction "2_2") (pintype "passive"))
    )
    (net (code "49") (name "/F6") (class "Default")
      (node (ref "Q30") (pin "1") (pinfunction "B_1") (pintype "passive"))
      (node (ref "R30") (pin "2") (pinfunction "2_2") (pintype "passive"))
    )
    (net (code "50") (name "/F6#") (class "Default")
      (node (ref "Q31") (pin "1") (pinfunction "B_1") (pintype "passive"))
      (node (ref "R31") (pin "2") (pinfunction "2_2") (pintype "passive"))
    )
    (net (code "51") (name "/F7") (class "Default")
      (node (ref "Q39") (pin "1") (pinfunction "B_1") (pintype "passive"))
      (node (ref "R39") (pin "2") (pinfunction "2_2") (pintype "passive"))
    )
    (net (code "52") (name "/F7#") (class "Default")
      (node (ref "Q38") (pin "1") (pinfunction "B_1") (pintype "passive"))
      (node (ref "R38") (pin "2") (pinfunction "2_2") (pintype "passive"))
    )
    (net (code "53") (name "/Fillin") (class "Default")
      (node (ref "Q76") (pin "1") (pinfunction "B_1") (pintype "passive"))
      (node (ref "R76") (pin "2") (pinfunction "2_2") (pintype "passive"))
    )
    (net (code "54") (name "/Finger") (class "Default")
      (node (ref "Q78") (pin "1") (pinfunction "B_1") (pintype "passive"))
      (node (ref "R78") (pin "2") (pinfunction "2_2") (pintype "passive"))
    )
    (net (code "55") (name "/G4") (class "Default")
      (node (ref "Q9") (pin "1") (pinfunction "B_1") (pintype "passive"))
      (node (ref "R9") (pin "2") (pinfunction "2_2") (pintype "passive"))
    )
    (net (code "56") (name "/G4#") (class "Default")
      (node (ref "Q8") (pin "1") (pinfunction "B_1") (pintype "passive"))
      (node (ref "R8") (pin "2") (pinfunction "2_2") (pintype "passive"))
    )
    (net (code "57") (name "/G5") (class "Default")
      (node (ref "Q20") (pin "1") (pinfunction "B_1") (pintype "passive"))
      (node (ref "R20") (pin "2") (pinfunction "2_2") (pintype "passive"))
    )
    (net (code "58") (name "/G5#") (class "Default")
      (node (ref "Q28") (pin "1") (pinfunction "B_1") (pintype "passive"))
      (node (ref "R28") (pin "2") (pinfunction "2_2") (pintype "passive"))
    )
    (net (code "59") (name "/G6") (class "Default")
      (node (ref "Q32") (pin "1") (pinfunction "B_1") (pintype "passive"))
      (node (ref "R32") (pin "2") (pinfunction "2_2") (pintype "passive"))
    )
    (net (code "60") (name "/G6#") (class "Default")
      (node (ref "Q33") (pin "1") (pinfunction "B_1") (pintype "passive"))
      (node (ref "R33") (pin "2") (pinfunction "2_2") (pintype "passive"))
    )
    (net (code "61") (name "/G7") (class "Default")
      (node (ref "Q37") (pin "1") (pinfunction "B_1") (pintype "passive"))
      (node (ref "R37") (pin "2") (pinfunction "2_2") (pintype "passive"))
    )
    (net (code "62") (name "/G7#") (class "Default")
      (node (ref "Q45") (pin "1") (pinfunction "B_1") (pintype "passive"))
      (node (ref "R45") (pin "2") (pinfunction "2_2") (pintype "passive"))
    )
    (net (code "63") (name "/Learn") (class "Default")
      (node (ref "Q83") (pin "1") (pinfunction "B_1") (pintype "passive"))
      (node (ref "R83") (pin "2") (pinfunction "2_2") (pintype "passive"))
    )
    (net (code "64") (name "/P00") (class "Default")
      (node (ref "Px1") (pin "1") (pinfunction "1_1") (pintype "passive"))
      (node (ref "Q13") (pin "3") (pinfunction "C_3") (pintype "passive"))
      (node (ref "Q21") (pin "3") (pinfunction "C_3") (pintype "passive"))
      (node (ref "Q29") (pin "3") (pinfunction "C_3") (pintype "passive"))
      (node (ref "Q37") (pin "3") (pinfunction "C_3") (pintype "passive"))
      (node (ref "Q45") (pin "3") (pinfunction "C_3") (pintype "passive"))
      (node (ref "Q5") (pin "3") (pinfunction "C_3") (pintype "passive"))
      (node (ref "Q53") (pin "3") (pinfunction "C_3") (pintype "passive"))
      (node (ref "Q61") (pin "3") (pinfunction "C_3") (pintype "passive"))
      (node (ref "Q69") (pin "3") (pinfunction "C_3") (pintype "passive"))
      (node (ref "Q77") (pin "3") (pinfunction "C_3") (pintype "passive"))
    )
    (net (code "65") (name "/P01") (class "Default")
      (node (ref "Px1") (pin "2") (pinfunction "2_2") (pintype "passive"))
      (node (ref "Q14") (pin "3") (pinfunction "C_3") (pintype "passive"))
      (node (ref "Q22") (pin "3") (pinfunction "C_3") (pintype "passive"))
      (node (ref "Q30") (pin "3") (pinfunction "C_3") (pintype "passive"))
      (node (ref "Q38") (pin "3") (pinfunction "C_3") (pintype "passive"))
      (node (ref "Q46") (pin "3") (pinfunction "C_3") (pintype "passive"))
      (node (ref "Q54") (pin "3") (pinfunction "C_3") (pintype "passive"))
      (node (ref "Q6") (pin "3") (pinfunction "C_3") (pintype "passive"))
      (node (ref "Q62") (pin "3") (pinfunction "C_3") (pintype "passive"))
      (node (ref "Q70") (pin "3") (pinfunction "C_3") (pintype "passive"))
      (node (ref "Q78") (pin "3") (pinfunction "C_3") (pintype "passive"))
    )
    (net (code "66") (name "/P02") (class "Default")
      (node (ref "Px1") (pin "3") (pinfunction "3_3") (pintype "passive"))
      (node (ref "Q15") (pin "3") (pinfunction "C_3") (pintype "passive"))
      (node (ref "Q23") (pin "3") (pinfunction "C_3") (pintype "passive"))
      (node (ref "Q31") (pin "3") (pinfunction "C_3") (pintype "passive"))
      (node (ref "Q39") (pin "3") (pinfunction "C_3") (pintype "passive"))
      (node (ref "Q47") (pin "3") (pinfunction "C_3") (pintype "passive"))
      (node (ref "Q55") (pin "3") (pinfunction "C_3") (pintype "passive"))
      (node (ref "Q63") (pin "3") (pinfunction "C_3") (pintype "passive"))
      (node (ref "Q7") (pin "3") (pinfunction "C_3") (pintype "passive"))
      (node (ref "Q71") (pin "3") (pinfunction "C_3") (pintype "passive"))
      (node (ref "Q79") (pin "3") (pinfunction "C_3") (pintype "passive"))
    )
    (net (code "67") (name "/P03") (class "Default")
      (node (ref "Px1") (pin "4") (pinfunction "4_4") (pintype "passive"))
      (node (ref "Q16") (pin "3") (pinfunction "C_3") (pintype "passive"))
      (node (ref "Q24") (pin "3") (pinfunction "C_3") (pintype "passive"))
      (node (ref "Q32") (pin "3") (pinfunction "C_3") (pintype "passive"))
      (node (ref "Q40") (pin "3") (pinfunction "C_3") (pintype "passive"))
      (node (ref "Q48") (pin "3") (pinfunction "C_3") (pintype "passive"))
      (node (ref "Q56") (pin "3") (pinfunction "C_3") (pintype "passive"))
      (node (ref "Q64") (pin "3") (pinfunction "C_3") (pintype "passive"))
      (node (ref "Q72") (pin "3") (pinfunction "C_3") (pintype "passive"))
      (node (ref "Q8") (pin "3") (pinfunction "C_3") (pintype "passive"))
      (node (ref "Q80") (pin "3") (pinfunction "C_3") (pintype "passive"))
    )
    (net (code "68") (name "/P04") (class "Default")
      (node (ref "Px1") (pin "5") (pinfunction "5_5") (pintype "passive"))
      (node (ref "Q1") (pin "3") (pinfunction "C_3") (pintype "passive"))
      (node (ref "Q17") (pin "3") (pinfunction "C_3") (pintype "passive"))
      (node (ref "Q25") (pin "3") (pinfunction "C_3") (pintype "passive"))
      (node (ref "Q33") (pin "3") (pinfunction "C_3") (pintype "passive"))
      (node (ref "Q41") (pin "3") (pinfunction "C_3") (pintype "passive"))
      (node (ref "Q49") (pin "3") (pinfunction "C_3") (pintype "passive"))
      (node (ref "Q57") (pin "3") (pinfunction "C_3") (pintype "passive"))
      (node (ref "Q65") (pin "3") (pinfunction "C_3") (pintype "passive"))
      (node (ref "Q73") (pin "3") (pinfunction "C_3") (pintype "passive"))
      (node (ref "Q81") (pin "3") (pinfunction "C_3") (pintype "passive"))
      (node (ref "Q9") (pin "3") (pinfunction "C_3") (pintype "passive"))
    )
    (net (code "69") (name "/P05") (class "Default")
      (node (ref "Px1") (pin "6") (pinfunction "6_6") (pintype "passive"))
      (node (ref "Q10") (pin "3") (pinfunction "C_3") (pintype "passive"))
      (node (ref "Q18") (pin "3") (pinfunction "C_3") (pintype "passive"))
      (node (ref "Q2") (pin "3") (pinfunction "C_3") (pintype "passive"))
      (node (ref "Q26") (pin "3") (pinfunction "C_3") (pintype "passive"))
      (node (ref "Q34") (pin "3") (pinfunction "C_3") (pintype "passive"))
      (node (ref "Q42") (pin "3") (pinfunction "C_3") (pintype "passive"))
      (node (ref "Q50") (pin "3") (pinfunction "C_3") (pintype "passive"))
      (node (ref "Q58") (pin "3") (pinfunction "C_3") (pintype "passive"))
      (node (ref "Q66") (pin "3") (pinfunction "C_3") (pintype "passive"))
      (node (ref "Q74") (pin "3") (pinfunction "C_3") (pintype "passive"))
      (node (ref "Q82") (pin "3") (pinfunction "C_3") (pintype "passive"))
    )
    (net (code "70") (name "/P06") (class "Default")
      (node (ref "Px1") (pin "7") (pinfunction "7_7") (pintype "passive"))
      (node (ref "Q11") (pin "3") (pinfunction "C_3") (pintype "passive"))
      (node (ref "Q19") (pin "3") (pinfunction "C_3") (pintype "passive"))
      (node (ref "Q27") (pin "3") (pinfunction "C_3") (pintype "passive"))
      (node (ref "Q3") (pin "3") (pinfunction "C_3") (pintype "passive"))
      (node (ref "Q35") (pin "3") (pinfunction "C_3") (pintype "passive"))
      (node (ref "Q43") (pin "3") (pinfunction "C_3") (pintype "passive"))
      (node (ref "Q51") (pin "3") (pinfunction "C_3") (pintype "passive"))
      (node (ref "Q59") (pin "3") (pinfunction "C_3") (pintype "passive"))
      (node (ref "Q67") (pin "3") (pinfunction "C_3") (pintype "passive"))
      (node (ref "Q75") (pin "3") (pinfunction "C_3") (pintype "passive"))
      (node (ref "Q83") (pin "3") (pinfunction "C_3") (pintype "passive"))
    )
    (net (code "71") (name "/P07") (class "Default")
      (node (ref "Px1") (pin "8") (pinfunction "8_8") (pintype "passive"))
      (node (ref "Q12") (pin "3") (pinfunction "C_3") (pintype "passive"))
      (node (ref "Q20") (pin "3") (pinfunction "C_3") (pintype "passive"))
      (node (ref "Q28") (pin "3") (pinfunction "C_3") (pintype "passive"))
      (node (ref "Q36") (pin "3") (pinfunction "C_3") (pintype "passive"))
      (node (ref "Q4") (pin "3") (pinfunction "C_3") (pintype "passive"))
      (node (ref "Q44") (pin "3") (pinfunction "C_3") (pintype "passive"))
      (node (ref "Q52") (pin "3") (pinfunction "C_3") (pintype "passive"))
      (node (ref "Q60") (pin "3") (pinfunction "C_3") (pintype "passive"))
      (node (ref "Q68") (pin "3") (pinfunction "C_3") (pintype "passive"))
      (node (ref "Q76") (pin "3") (pinfunction "C_3") (pintype "passive"))
      (node (ref "Q84") (pin "3") (pinfunction "C_3") (pintype "passive"))
    )
    (net (code "72") (name "/P11") (class "Default")
      (node (ref "D1") (pin "2") (pinfunction "K_2") (pintype "passive"))
      (node (ref "Py1") (pin "1") (pinfunction "1_1") (pintype "passive"))
    )
    (net (code "73") (name "/P12") (class "Default")
      (node (ref "D2") (pin "2") (pinfunction "K_2") (pintype "passive"))
      (node (ref "Py1") (pin "2") (pinfunction "2_2") (pintype "passive"))
    )
    (net (code "74") (name "/P13") (class "Default")
      (node (ref "D3") (pin "2") (pinfunction "K_2") (pintype "passive"))
      (node (ref "Py1") (pin "3") (pinfunction "3_3") (pintype "passive"))
    )
    (net (code "75") (name "/P14") (class "Default")
      (node (ref "D4") (pin "2") (pinfunction "K_2") (pintype "passive"))
      (node (ref "Py1") (pin "4") (pinfunction "4_4") (pintype "passive"))
    )
    (net (code "76") (name "/P15") (class "Default")
      (node (ref "D5") (pin "2") (pinfunction "K_2") (pintype "passive"))
      (node (ref "Py1") (pin "5") (pinfunction "5_5") (pintype "passive"))
    )
    (net (code "77") (name "/P16") (class "Default")
      (node (ref "D6") (pin "2") (pinfunction "K_2") (pintype "passive"))
      (node (ref "Py1") (pin "6") (pinfunction "6_6") (pintype "passive"))
    )
    (net (code "78") (name "/P17") (class "Default")
      (node (ref "D7") (pin "2") (pinfunction "K_2") (pintype "passive"))
      (node (ref "Py1") (pin "7") (pinfunction "7_7") (pintype "passive"))
    )
    (net (code "79") (name "/P24") (class "Default")
      (node (ref "D11") (pin "2") (pinfunction "K_2") (pintype "passive"))
      (node (ref "Py1") (pin "11") (pinfunction "11_11") (pintype "passive"))
    )
    (net (code "80") (name "/P25") (class "Default")
      (node (ref "D10") (pin "2") (pinfunction "K_2") (pintype "passive"))
      (node (ref "Py1") (pin "10") (pinfunction "10_10") (pintype "passive"))
    )
    (net (code "81") (name "/P26") (class "Default")
      (node (ref "D9") (pin "2") (pinfunction "K_2") (pintype "passive"))
      (node (ref "Py1") (pin "9") (pinfunction "9_9") (pintype "passive"))
    )
    (net (code "82") (name "/P27") (class "Default")
      (node (ref "D8") (pin "2") (pinfunction "K_2") (pintype "passive"))
      (node (ref "Py1") (pin "8") (pinfunction "8_8") (pintype "passive"))
    )
    (net (code "83") (name "/RHY1") (class "Default")
      (node (ref "Q61") (pin "1") (pinfunction "B_1") (pintype "passive"))
      (node (ref "R61") (pin "2") (pinfunction "2_2") (pintype "passive"))
    )
    (net (code "84") (name "/RHY2") (class "Default")
      (node (ref "Q62") (pin "1") (pinfunction "B_1") (pintype "passive"))
      (node (ref "R62") (pin "2") (pinfunction "2_2") (pintype "passive"))
    )
    (net (code "85") (name "/RHY3") (class "Default")
      (node (ref "Q55") (pin "1") (pinfunction "B_1") (pintype "passive"))
      (node (ref "R55") (pin "2") (pinfunction "2_2") (pintype "passive"))
    )
    (net (code "86") (name "/RHY4") (class "Default")
      (node (ref "Q56") (pin "1") (pinfunction "B_1") (pintype "passive"))
      (node (ref "R56") (pin "2") (pinfunction "2_2") (pintype "passive"))
    )
    (net (code "87") (name "/RHY5") (class "Default")
      (node (ref "Q65") (pin "1") (pinfunction "B_1") (pintype "passive"))
      (node (ref "R65") (pin "2") (pinfunction "2_2") (pintype "passive"))
    )
    (net (code "88") (name "/RHY6") (class "Default")
      (node (ref "Q66") (pin "1") (pinfunction "B_1") (pintype "passive"))
      (node (ref "R66") (pin "2") (pinfunction "2_2") (pintype "passive"))
    )
    (net (code "89") (name "/RHY7") (class "Default")
      (node (ref "Q67") (pin "1") (pinfunction "B_1") (pintype "passive"))
      (node (ref "R67") (pin "2") (pinfunction "2_2") (pintype "passive"))
    )
    (net (code "90") (name "/RHY8") (class "Default")
      (node (ref "Q68") (pin "1") (pinfunction "B_1") (pintype "passive"))
      (node (ref "R68") (pin "2") (pinfunction "2_2") (pintype "passive"))
    )
    (net (code "91") (name "/RHY9") (class "Default")
      (node (ref "Q63") (pin "1") (pinfunction "B_1") (pintype "passive"))
      (node (ref "R63") (pin "2") (pinfunction "2_2") (pintype "passive"))
    )
    (net (code "92") (name "/RHY10") (class "Default")
      (node (ref "Q64") (pin "1") (pinfunction "B_1") (pintype "passive"))
      (node (ref "R64") (pin "2") (pinfunction "2_2") (pintype "passive"))
    )
    (net (code "93") (name "/Record") (class "Default")
      (node (ref "Q50") (pin "1") (pinfunction "B_1") (pintype "passive"))
      (node (ref "R50") (pin "2") (pinfunction "2_2") (pintype "passive"))
    )
    (net (code "94") (name "/Replay") (class "Default")
      (node (ref "Q74") (pin "1") (pinfunction "B_1") (pintype "passive"))
      (node (ref "R74") (pin "2") (pinfunction "2_2") (pintype "passive"))
    )
    (net (code "95") (name "/Rhy_edit") (class "Default")
      (node (ref "Q69") (pin "1") (pinfunction "B_1") (pintype "passive"))
      (node (ref "R69") (pin "2") (pinfunction "2_2") (pintype "passive"))
    )
    (net (code "96") (name "/STOP") (class "Default")
      (node (ref "Q73") (pin "1") (pinfunction "B_1") (pintype "passive"))
      (node (ref "R73") (pin "2") (pinfunction "2_2") (pintype "passive"))
    )
    (net (code "97") (name "/Single") (class "Default")
      (node (ref "Q77") (pin "1") (pinfunction "B_1") (pintype "passive"))
      (node (ref "R77") (pin "2") (pinfunction "2_2") (pintype "passive"))
    )
    (net (code "98") (name "/Tone1") (class "Default")
      (node (ref "Q52") (pin "1") (pinfunction "B_1") (pintype "passive"))
      (node (ref "R52") (pin "2") (pinfunction "2_2") (pintype "passive"))
    )
    (net (code "99") (name "/Tone2") (class "Default")
      (node (ref "Q51") (pin "1") (pinfunction "B_1") (pintype "passive"))
      (node (ref "R51") (pin "2") (pinfunction "2_2") (pintype "passive"))
    )
    (net (code "100") (name "/VOL+") (class "Default")
      (node (ref "Q81") (pin "1") (pinfunction "B_1") (pintype "passive"))
      (node (ref "R81") (pin "2") (pinfunction "2_2") (pintype "passive"))
    )
    (net (code "101") (name "/VOL-") (class "Default")
      (node (ref "Q82") (pin "1") (pinfunction "B_1") (pintype "passive"))
      (node (ref "R82") (pin "2") (pinfunction "2_2") (pintype "passive"))
    )
    (net (code "102") (name "/tempo+") (class "Default")
      (node (ref "Q79") (pin "1") (pinfunction "B_1") (pintype "passive"))
      (node (ref "R79") (pin "2") (pinfunction "2_2") (pintype "passive"))
    )
    (net (code "103") (name "/tempo-") (class "Default")
      (node (ref "Q80") (pin "1") (pinfunction "B_1") (pintype "passive"))
      (node (ref "R80") (pin "2") (pinfunction "2_2") (pintype "passive"))
    )
    (net (code "104") (name "GND") (class "Default")
      (node (ref "Px1") (pin "10") (pinfunction "10_10") (pintype "passive"))
      (node (ref "R1") (pin "1") (pinfunction "1_1") (pintype "passive"))
      (node (ref "R10") (pin "1") (pinfunction "1_1") (pintype "passive"))
      (node (ref "R11") (pin "1") (pinfunction "1_1") (pintype "passive"))
      (node (ref "R12") (pin "1") (pinfunction "1_1") (pintype "passive"))
      (node (ref "R13") (pin "1") (pinfunction "1_1") (pintype "passive"))
      (node (ref "R14") (pin "1") (pinfunction "1_1") (pintype "passive"))
      (node (ref "R15") (pin "1") (pinfunction "1_1") (pintype "passive"))
      (node (ref "R16") (pin "1") (pinfunction "1_1") (pintype "passive"))
      (node (ref "R17") (pin "1") (pinfunction "1_1") (pintype "passive"))
      (node (ref "R18") (pin "1") (pinfunction "1_1") (pintype "passive"))
      (node (ref "R19") (pin "1") (pinfunction "1_1") (pintype "passive"))
      (node (ref "R2") (pin "1") (pinfunction "1_1") (pintype "passive"))
      (node (ref "R20") (pin "1") (pinfunction "1_1") (pintype "passive"))
      (node (ref "R21") (pin "1") (pinfunction "1_1") (pintype "passive"))
      (node (ref "R22") (pin "1") (pinfunction "1_1") (pintype "passive"))
      (node (ref "R23") (pin "1") (pinfunction "1_1") (pintype "passive"))
      (node (ref "R24") (pin "1") (pinfunction "1_1") (pintype "passive"))
      (node (ref "R25") (pin "1") (pinfunction "1_1") (pintype "passive"))
      (node (ref "R26") (pin "1") (pinfunction "1_1") (pintype "passive"))
      (node (ref "R27") (pin "1") (pinfunction "1_1") (pintype "passive"))
      (node (ref "R28") (pin "1") (pinfunction "1_1") (pintype "passive"))
      (node (ref "R29") (pin "1") (pinfunction "1_1") (pintype "passive"))
      (node (ref "R3") (pin "1") (pinfunction "1_1") (pintype "passive"))
      (node (ref "R30") (pin "1") (pinfunction "1_1") (pintype "passive"))
      (node (ref "R31") (pin "1") (pinfunction "1_1") (pintype "passive"))
      (node (ref "R32") (pin "1") (pinfunction "1_1") (pintype "passive"))
      (node (ref "R33") (pin "1") (pinfunction "1_1") (pintype "passive"))
      (node (ref "R34") (pin "1") (pinfunction "1_1") (pintype "passive"))
      (node (ref "R35") (pin "1") (pinfunction "1_1") (pintype "passive"))
      (node (ref "R36") (pin "1") (pinfunction "1_1") (pintype "passive"))
      (node (ref "R37") (pin "1") (pinfunction "1_1") (pintype "passive"))
      (node (ref "R38") (pin "1") (pinfunction "1_1") (pintype "passive"))
      (node (ref "R39") (pin "1") (pinfunction "1_1") (pintype "passive"))
      (node (ref "R4") (pin "1") (pinfunction "1_1") (pintype "passive"))
      (node (ref "R40") (pin "1") (pinfunction "1_1") (pintype "passive"))
      (node (ref "R41") (pin "1") (pinfunction "1_1") (pintype "passive"))
      (node (ref "R42") (pin "1") (pinfunction "1_1") (pintype "passive"))
      (node (ref "R43") (pin "1") (pinfunction "1_1") (pintype "passive"))
      (node (ref "R44") (pin "1") (pinfunction "1_1") (pintype "passive"))
      (node (ref "R45") (pin "1") (pinfunction "1_1") (pintype "passive"))
      (node (ref "R46") (pin "1") (pinfunction "1_1") (pintype "passive"))
      (node (ref "R47") (pin "1") (pinfunction "1_1") (pintype "passive"))
      (node (ref "R48") (pin "1") (pinfunction "1_1") (pintype "passive"))
      (node (ref "R49") (pin "1") (pinfunction "1_1") (pintype "passive"))
      (node (ref "R5") (pin "1") (pinfunction "1_1") (pintype "passive"))
      (node (ref "R50") (pin "1") (pinfunction "1_1") (pintype "passive"))
      (node (ref "R51") (pin "1") (pinfunction "1_1") (pintype "passive"))
      (node (ref "R52") (pin "1") (pinfunction "1_1") (pintype "passive"))
      (node (ref "R53") (pin "1") (pinfunction "1_1") (pintype "passive"))
      (node (ref "R54") (pin "1") (pinfunction "1_1") (pintype "passive"))
      (node (ref "R55") (pin "1") (pinfunction "1_1") (pintype "passive"))
      (node (ref "R56") (pin "1") (pinfunction "1_1") (pintype "passive"))
      (node (ref "R57") (pin "1") (pinfunction "1_1") (pintype "passive"))
      (node (ref "R58") (pin "1") (pinfunction "1_1") (pintype "passive"))
      (node (ref "R59") (pin "1") (pinfunction "1_1") (pintype "passive"))
      (node (ref "R6") (pin "1") (pinfunction "1_1") (pintype "passive"))
      (node (ref "R60") (pin "1") (pinfunction "1_1") (pintype "passive"))
      (node (ref "R61") (pin "1") (pinfunction "1_1") (pintype "passive"))
      (node (ref "R62") (pin "1") (pinfunction "1_1") (pintype "passive"))
      (node (ref "R63") (pin "1") (pinfunction "1_1") (pintype "passive"))
      (node (ref "R64") (pin "1") (pinfunction "1_1") (pintype "passive"))
      (node (ref "R65") (pin "1") (pinfunction "1_1") (pintype "passive"))
      (node (ref "R66") (pin "1") (pinfunction "1_1") (pintype "passive"))
      (node (ref "R67") (pin "1") (pinfunction "1_1") (pintype "passive"))
      (node (ref "R68") (pin "1") (pinfunction "1_1") (pintype "passive"))
      (node (ref "R69") (pin "1") (pinfunction "1_1") (pintype "passive"))
      (node (ref "R7") (pin "1") (pinfunction "1_1") (pintype "passive"))
      (node (ref "R70") (pin "1") (pinfunction "1_1") (pintype "passive"))
      (node (ref "R71") (pin "1") (pinfunction "1_1") (pintype "passive"))
      (node (ref "R72") (pin "1") (pinfunction "1_1") (pintype "passive"))
      (node (ref "R73") (pin "1") (pinfunction "1_1") (pintype "passive"))
      (node (ref "R74") (pin "1") (pinfunction "1_1") (pintype "passive"))
      (node (ref "R75") (pin "1") (pinfunction "1_1") (pintype "passive"))
      (node (ref "R76") (pin "1") (pinfunction "1_1") (pintype "passive"))
      (node (ref "R77") (pin "1") (pinfunction "1_1") (pintype "passive"))
      (node (ref "R78") (pin "1") (pinfunction "1_1") (pintype "passive"))
      (node (ref "R79") (pin "1") (pinfunction "1_1") (pintype "passive"))
      (node (ref "R8") (pin "1") (pinfunction "1_1") (pintype "passive"))
      (node (ref "R80") (pin "1") (pinfunction "1_1") (pintype "passive"))
      (node (ref "R81") (pin "1") (pinfunction "1_1") (pintype "passive"))
      (node (ref "R82") (pin "1") (pinfunction "1_1") (pintype "passive"))
      (node (ref "R83") (pin "1") (pinfunction "1_1") (pintype "passive"))
      (node (ref "R84") (pin "1") (pinfunction "1_1") (pintype "passive"))
      (node (ref "R9") (pin "1") (pinfunction "1_1") (pintype "passive"))
    )
    (net (code "105") (name "Net-(D1-A)") (class "Default")
      (node (ref "D1") (pin "1") (pinfunction "A_1") (pintype "passive"))
      (node (ref "Q1") (pin "2") (pinfunction "E_2") (pintype "passive"))
      (node (ref "Q2") (pin "2") (pinfunction "E_2") (pintype "passive"))
      (node (ref "Q3") (pin "2") (pinfunction "E_2") (pintype "passive"))
      (node (ref "Q4") (pin "2") (pinfunction "E_2") (pintype "passive"))
    )
    (net (code "106") (name "Net-(D2-A)") (class "Default")
      (node (ref "D2") (pin "1") (pinfunction "A_1") (pintype "passive"))
      (node (ref "Q10") (pin "2") (pinfunction "E_2") (pintype "passive"))
      (node (ref "Q11") (pin "2") (pinfunction "E_2") (pintype "passive"))
      (node (ref "Q12") (pin "2") (pinfunction "E_2") (pintype "passive"))
      (node (ref "Q5") (pin "2") (pinfunction "E_2") (pintype "passive"))
      (node (ref "Q6") (pin "2") (pinfunction "E_2") (pintype "passive"))
      (node (ref "Q7") (pin "2") (pinfunction "E_2") (pintype "passive"))
      (node (ref "Q8") (pin "2") (pinfunction "E_2") (pintype "passive"))
      (node (ref "Q9") (pin "2") (pinfunction "E_2") (pintype "passive"))
    )
    (net (code "107") (name "Net-(D3-A)") (class "Default")
      (node (ref "D3") (pin "1") (pinfunction "A_1") (pintype "passive"))
      (node (ref "Q13") (pin "2") (pinfunction "E_2") (pintype "passive"))
      (node (ref "Q14") (pin "2") (pinfunction "E_2") (pintype "passive"))
      (node (ref "Q15") (pin "2") (pinfunction "E_2") (pintype "passive"))
      (node (ref "Q16") (pin "2") (pinfunction "E_2") (pintype "passive"))
      (node (ref "Q17") (pin "2") (pinfunction "E_2") (pintype "passive"))
      (node (ref "Q18") (pin "2") (pinfunction "E_2") (pintype "passive"))
      (node (ref "Q19") (pin "2") (pinfunction "E_2") (pintype "passive"))
      (node (ref "Q20") (pin "2") (pinfunction "E_2") (pintype "passive"))
    )
    (net (code "108") (name "Net-(D4-A)") (class "Default")
      (node (ref "D4") (pin "1") (pinfunction "A_1") (pintype "passive"))
      (node (ref "Q21") (pin "2") (pinfunction "E_2") (pintype "passive"))
      (node (ref "Q22") (pin "2") (pinfunction "E_2") (pintype "passive"))
      (node (ref "Q23") (pin "2") (pinfunction "E_2") (pintype "passive"))
      (node (ref "Q24") (pin "2") (pinfunction "E_2") (pintype "passive"))
      (node (ref "Q25") (pin "2") (pinfunction "E_2") (pintype "passive"))
      (node (ref "Q26") (pin "2") (pinfunction "E_2") (pintype "passive"))
      (node (ref "Q27") (pin "2") (pinfunction "E_2") (pintype "passive"))
      (node (ref "Q28") (pin "2") (pinfunction "E_2") (pintype "passive"))
    )
    (net (code "109") (name "Net-(D5-A)") (class "Default")
      (node (ref "D5") (pin "1") (pinfunction "A_1") (pintype "passive"))
      (node (ref "Q29") (pin "2") (pinfunction "E_2") (pintype "passive"))
      (node (ref "Q30") (pin "2") (pinfunction "E_2") (pintype "passive"))
      (node (ref "Q31") (pin "2") (pinfunction "E_2") (pintype "passive"))
      (node (ref "Q32") (pin "2") (pinfunction "E_2") (pintype "passive"))
      (node (ref "Q33") (pin "2") (pinfunction "E_2") (pintype "passive"))
      (node (ref "Q34") (pin "2") (pinfunction "E_2") (pintype "passive"))
      (node (ref "Q35") (pin "2") (pinfunction "E_2") (pintype "passive"))
      (node (ref "Q36") (pin "2") (pinfunction "E_2") (pintype "passive"))
    )
    (net (code "110") (name "Net-(D6-A)") (class "Default")
      (node (ref "D6") (pin "1") (pinfunction "A_1") (pintype "passive"))
      (node (ref "Q37") (pin "2") (pinfunction "E_2") (pintype "passive"))
      (node (ref "Q38") (pin "2") (pinfunction "E_2") (pintype "passive"))
      (node (ref "Q39") (pin "2") (pinfunction "E_2") (pintype "passive"))
      (node (ref "Q40") (pin "2") (pinfunction "E_2") (pintype "passive"))
      (node (ref "Q41") (pin "2") (pinfunction "E_2") (pintype "passive"))
      (node (ref "Q42") (pin "2") (pinfunction "E_2") (pintype "passive"))
      (node (ref "Q43") (pin "2") (pinfunction "E_2") (pintype "passive"))
      (node (ref "Q44") (pin "2") (pinfunction "E_2") (pintype "passive"))
    )
    (net (code "111") (name "Net-(D7-A)") (class "Default")
      (node (ref "D7") (pin "1") (pinfunction "A_1") (pintype "passive"))
      (node (ref "Q45") (pin "2") (pinfunction "E_2") (pintype "passive"))
      (node (ref "Q46") (pin "2") (pinfunction "E_2") (pintype "passive"))
      (node (ref "Q47") (pin "2") (pinfunction "E_2") (pintype "passive"))
      (node (ref "Q48") (pin "2") (pinfunction "E_2") (pintype "passive"))
      (node (ref "Q49") (pin "2") (pinfunction "E_2") (pintype "passive"))
      (node (ref "Q50") (pin "2") (pinfunction "E_2") (pintype "passive"))
      (node (ref "Q51") (pin "2") (pinfunction "E_2") (pintype "passive"))
      (node (ref "Q52") (pin "2") (pinfunction "E_2") (pintype "passive"))
    )
    (net (code "112") (name "Net-(D8-A)") (class "Default")
      (node (ref "D8") (pin "1") (pinfunction "A_1") (pintype "passive"))
      (node (ref "Q53") (pin "2") (pinfunction "E_2") (pintype "passive"))
      (node (ref "Q54") (pin "2") (pinfunction "E_2") (pintype "passive"))
      (node (ref "Q55") (pin "2") (pinfunction "E_2") (pintype "passive"))
      (node (ref "Q56") (pin "2") (pinfunction "E_2") (pintype "passive"))
      (node (ref "Q57") (pin "2") (pinfunction "E_2") (pintype "passive"))
      (node (ref "Q58") (pin "2") (pinfunction "E_2") (pintype "passive"))
      (node (ref "Q59") (pin "2") (pinfunction "E_2") (pintype "passive"))
      (node (ref "Q60") (pin "2") (pinfunction "E_2") (pintype "passive"))
    )
    (net (code "113") (name "Net-(D9-A)") (class "Default")
      (node (ref "D9") (pin "1") (pinfunction "A_1") (pintype "passive"))
      (node (ref "Q61") (pin "2") (pinfunction "E_2") (pintype "passive"))
      (node (ref "Q62") (pin "2") (pinfunction "E_2") (pintype "passive"))
      (node (ref "Q63") (pin "2") (pinfunction "E_2") (pintype "passive"))
      (node (ref "Q64") (pin "2") (pinfunction "E_2") (pintype "passive"))
      (node (ref "Q65") (pin "2") (pinfunction "E_2") (pintype "passive"))
      (node (ref "Q66") (pin "2") (pinfunction "E_2") (pintype "passive"))
      (node (ref "Q67") (pin "2") (pinfunction "E_2") (pintype "passive"))
      (node (ref "Q68") (pin "2") (pinfunction "E_2") (pintype "passive"))
    )
    (net (code "114") (name "Net-(D10-A)") (class "Default")
      (node (ref "D10") (pin "1") (pinfunction "A_1") (pintype "passive"))
      (node (ref "Q69") (pin "2") (pinfunction "E_2") (pintype "passive"))
      (node (ref "Q70") (pin "2") (pinfunction "E_2") (pintype "passive"))
      (node (ref "Q71") (pin "2") (pinfunction "E_2") (pintype "passive"))
      (node (ref "Q72") (pin "2") (pinfunction "E_2") (pintype "passive"))
      (node (ref "Q73") (pin "2") (pinfunction "E_2") (pintype "passive"))
      (node (ref "Q74") (pin "2") (pinfunction "E_2") (pintype "passive"))
      (node (ref "Q75") (pin "2") (pinfunction "E_2") (pintype "passive"))
      (node (ref "Q76") (pin "2") (pinfunction "E_2") (pintype "passive"))
    )
    (net (code "115") (name "Net-(D11-A)") (class "Default")
      (node (ref "D11") (pin "1") (pinfunction "A_1") (pintype "passive"))
      (node (ref "Q77") (pin "2") (pinfunction "E_2") (pintype "passive"))
      (node (ref "Q78") (pin "2") (pinfunction "E_2") (pintype "passive"))
      (node (ref "Q79") (pin "2") (pinfunction "E_2") (pintype "passive"))
      (node (ref "Q80") (pin "2") (pinfunction "E_2") (pintype "passive"))
      (node (ref "Q81") (pin "2") (pinfunction "E_2") (pintype "passive"))
      (node (ref "Q82") (pin "2") (pinfunction "E_2") (pintype "passive"))
      (node (ref "Q83") (pin "2") (pinfunction "E_2") (pintype "passive"))
      (node (ref "Q84") (pin "2") (pinfunction "E_2") (pintype "passive"))
    )
    (net (code "116") (name "VCC") (class "Default")
      (node (ref "Px1") (pin "9") (pinfunction "9_9") (pintype "passive"))
    )
    (net (code "117") (name "unconnected-(Py1-Pad12)") (class "Default")
      (node (ref "Py1") (pin "12") (pinfunction "12_12") (pintype "passive"))
    )
  )
)
